# Buck.net
KiCad netlist of a schematic drawn in Altium Designer
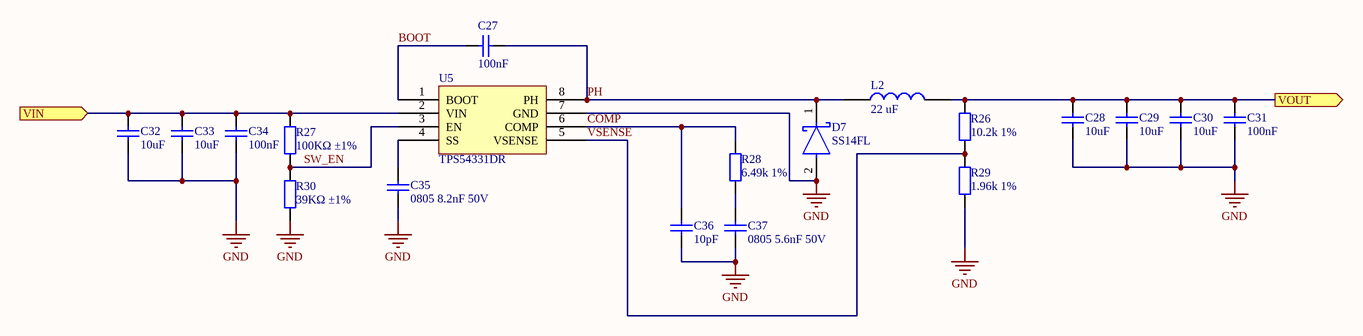
[diagram p0: Buck.SchDoc]

(export (version "E")
  (design (tool "Eeschema 10.0.6"))
  (components
    (comp (ref "C27")
      (value "100nF")
      (footprint "0603_C")
      (description "Chip capacitors")
      (fields (field (name "MANUFACTURER") "YAGEO") (field (name "PARTNUMBER") "CC0603KRX7R9BB104"))
      (libsource (lib "Miscellaneous Devices LC") (part "0603 100nF (104) 10% 50V"))
    )
    (comp (ref "C28")
      (value "10uF")
      (footprint "0603_C")
      (description "Chip capacitors")
      (fields
        (field (name "MANUFACTURER") "Samsung Electro-Mechanics")
        (field (name "PARTNUMBER") "CL10A106KP8NNNC")
      )
      (libsource (lib "Miscellaneous Devices LC") (part "0603 10uF (106) 10% 10V"))
    )
    (comp (ref "C29")
      (value "10uF")
      (footprint "0603_C")
      (description "Chip capacitors")
      (fields
        (field (name "MANUFACTURER") "Samsung Electro-Mechanics")
        (field (name "PARTNUMBER") "CL10A106KP8NNNC")
      )
      (libsource (lib "Miscellaneous Devices LC") (part "0603 10uF (106) 10% 10V"))
    )
    (comp (ref "C30")
      (value "10uF")
      (footprint "0603_C")
      (description "Chip capacitors")
      (fields
        (field (name "MANUFACTURER") "Samsung Electro-Mechanics")
        (field (name "PARTNUMBER") "CL10A106KP8NNNC")
      )
      (libsource (lib "Miscellaneous Devices LC") (part "0603 10uF (106) 10% 10V"))
    )
    (comp (ref "C31")
      (value "100nF")
      (footprint "0603_C")
      (description "Chip capacitors")
      (fields (field (name "MANUFACTURER") "YAGEO") (field (name "PARTNUMBER") "CC0603KRX7R9BB104"))
      (libsource (lib "Miscellaneous Devices LC") (part "0603 100nF (104) 10% 50V"))
    )
    (comp (ref "C32")
      (value "10uF")
      (footprint "0805_C")
      (description "Chip capacitors")
      (fields
        (field (name "MANUFACTURER") "Samsung Electro-Mechanics")
        (field (name "PARTNUMBER") "CL21A106KAYNNNE")
      )
      (libsource (lib "Miscellaneous Devices LC") (part "0805 10uF (106) 10% 25V"))
    )
    (comp (ref "C33")
      (value "10uF")
      (footprint "0805_C")
      (description "Chip capacitors")
      (fields
        (field (name "MANUFACTURER") "Samsung Electro-Mechanics")
        (field (name "PARTNUMBER") "CL21A106KAYNNNE")
      )
      (libsource (lib "Miscellaneous Devices LC") (part "0805 10uF (106) 10% 25V"))
    )
    (comp (ref "C34")
      (value "100nF")
      (footprint "0603_C")
      (description "Chip capacitors")
      (fields (field (name "MANUFACTURER") "YAGEO") (field (name "PARTNUMBER") "CC0603KRX7R9BB104"))
      (libsource (lib "Miscellaneous Devices LC") (part "0603 100nF (104) 10% 50V"))
    )
    (comp (ref "C35")
      (value "0805 8.2nF 50V")
      (footprint "Miscellaneous Devices LC:0805_C")
      (fields (field (name "PARTNUMBER") "CL21B822KBANNNC"))
      (libsource (lib "misc") (part "0805 8.2nF 50V"))
    )
    (comp (ref "C36")
      (value "10pF")
      (footprint "0603_C")
      (description "Chip capacitors")
      (fields
        (field (name "MANUFACTURER") "Samsung Electro-Mechanics")
        (field (name "PARTNUMBER") "CL10C100JB8NNNC")
      )
      (libsource (lib "Miscellaneous Devices LC") (part "0603 10pF (100) 5% 50V"))
    )
    (comp (ref "C37")
      (value "0805 5.6nF 50V")
      (footprint "Miscellaneous Devices LC:0805_C")
      (fields (field (name "PARTNUMBER") "CL21B562KBANNNC"))
      (libsource (lib "misc") (part "0805 5.6nF 50V"))
    )
    (comp (ref "D7")
      (value "SS14FL")
      (footprint "FP-425AD-MFG")
      (description "DIODE SCHOTTKY 40V 1A SOD123F")
      (fields
        (field (name "MANUFACTURER") "ON Semiconductor")
        (field (name "OCTOPART") "https://octopart.com/ss14fl-on+semiconductor-84331601")
      )
      (libsource (lib "Altium Content Vault") (part "c1678fac7984e62e0809fbf79c06691"))
    )
    (comp (ref "L2")
      (value "22 uF")
      (footprint "DR74:COBU-DR74-4R7-R_V")
      (libsource (lib "SWRB1204S-220MT") (part "SRP6540-5R6M"))
    )
    (comp (ref "R26")
      (value "10.2k 1%")
      (footprint "Miscellaneous Devices LC:1206_R")
      (fields (field (name "PARTNUMBER") "1206W4F1022T5E"))
      (libsource (lib "misc") (part "1206 10.2k 1%"))
    )
    (comp (ref "R27")
      (value "100KΩ ±1%")
      (footprint "0805_R")
      (description "Chip resistor")
      (fields (field (name "MANUFACTURER") "Uniroyal Elec") (field (name "POWER") "1/8W"))
      (libsource (lib "Miscellaneous Devices LC") (part "0805 100K (1003) 1%"))
    )
    (comp (ref "R28")
      (value "6.49k 1%")
      (footprint "Miscellaneous Devices LC:0805_R")
      (fields (field (name "PARTNUMBER") "0805W8F6491T5E"))
      (libsource (lib "misc") (part "0805 6.49k 1%"))
    )
    (comp (ref "R29")
      (value "1.96k 1%")
      (footprint "Miscellaneous Devices LC:1206_R")
      (fields (field (name "PARTNUMBER") "1206W4F1022T5E"))
      (libsource (lib "misc") (part "1206 1.96k 1%"))
    )
    (comp (ref "R30")
      (value "39KΩ ±1%")
      (footprint "0805_R")
      (description "Chip resistor")
      (fields (field (name "MANUFACTURER") "Uniroyal Elec") (field (name "POWER") "1/8W"))
      (libsource (lib "Miscellaneous Devices LC") (part "0805 39K (3902) 1%"))
    )
    (comp (ref "U5")
      (value "TPS54331DR")
      (footprint "SOIC-8_150mil")
      (description "DC-DC芯片")
      (libsource (lib "Miscellaneous Devices LC") (part "TPS54331DR_[C9865]"))
    )
  )
  (nets
    (net (code "1") (name "/BOOT") (class "Default")
      (node (ref "C27") (pin "2") (pinfunction "2_2") (pintype "passive"))
      (node (ref "U5") (pin "1") (pinfunction "BOOT_1") (pintype "passive"))
    )
    (net (code "2") (name "/COMP") (class "Default")
      (node (ref "C36") (pin "2") (pinfunction "2_2") (pintype "passive"))
      (node (ref "R28") (pin "2") (pinfunction "2_2") (pintype "passive"))
      (node (ref "U5") (pin "6") (pinfunction "COMP_6") (pintype "passive"))
    )
    (net (code "3") (name "/PH") (class "Default")
      (node (ref "C27") (pin "1") (pinfunction "1_1") (pintype "passive"))
      (node (ref "D7") (pin "1") (pinfunction "C_1") (pintype "passive"))
      (node (ref "L2") (pin "1") (pinfunction "1_1") (pintype "passive"))
      (node (ref "U5") (pin "8") (pinfunction "PH_8") (pintype "passive"))
    )
    (net (code "4") (name "/SW_EN") (class "Default")
      (node (ref "R27") (pin "2") (pinfunction "2_2") (pintype "passive"))
      (node (ref "R30") (pin "2") (pinfunction "2_2") (pintype "passive"))
      (node (ref "U5") (pin "3") (pinfunction "EN_3") (pintype "passive"))
    )
    (net (code "5") (name "/VIN") (class "Default")
      (node (ref "C32") (pin "2") (pinfunction "2_2") (pintype "passive"))
      (node (ref "C33") (pin "2") (pinfunction "2_2") (pintype "passive"))
      (node (ref "C34") (pin "2") (pinfunction "2_2") (pintype "passive"))
      (node (ref "R27") (pin "1") (pinfunction "1_1") (pintype "passive"))
      (node (ref "U5") (pin "2") (pinfunction "VIN_2") (pintype "passive"))
    )
    (net (code "6") (name "/VOUT") (class "Default")
      (node (ref "C28") (pin "2") (pinfunction "2_2") (pintype "passive"))
      (node (ref "C29") (pin "2") (pinfunction "2_2") (pintype "passive"))
      (node (ref "C30") (pin "2") (pinfunction "2_2") (pintype "passive"))
      (node (ref "C31") (pin "2") (pinfunction "2_2") (pintype "passive"))
      (node (ref "L2") (pin "2") (pinfunction "2_2") (pintype "passive"))
      (node (ref "R26") (pin "1") (pinfunction "1_1") (pintype "passive"))
    )
    (net (code "7") (name "/VSENSE") (class "Default")
      (node (ref "R26") (pin "2") (pinfunction "2_2") (pintype "passive"))
      (node (ref "R29") (pin "2") (pinfunction "2_2") (pintype "passive"))
      (node (ref "U5") (pin "5") (pinfunction "VSENSE_5") (pintype "passive"))
    )
    (net (code "8") (name "GND") (class "Default")
      (node (ref "C28") (pin "1") (pinfunction "1_1") (pintype "passive"))
      (node (ref "C29") (pin "1") (pinfunction "1_1") (pintype "passive"))
      (node (ref "C30") (pin "1") (pinfunction "1_1") (pintype "passive"))
      (node (ref "C31") (pin "1") (pinfunction "1_1") (pintype "passive"))
      (node (ref "C32") (pin "1") (pinfunction "1_1") (pintype "passive"))
      (node (ref "C33") (pin "1") (pinfunction "1_1") (pintype "passive"))
      (node (ref "C34") (pin "1") (pinfunction "1_1") (pintype "passive"))
      (node (ref "C35") (pin "1") (pinfunction "1_1") (pintype "passive"))
      (node (ref "C36") (pin "1") (pinfunction "1_1") (pintype "passive"))
      (node (ref "C37") (pin "1") (pinfunction "1_1") (pintype "passive"))
      (node (ref "D7") (pin "2") (pinfunction "A_2") (pintype "passive"))
      (node (ref "R29") (pin "1") (pinfunction "1_1") (pintype "passive"))
      (node (ref "R30") (pin "1") (pinfunction "1_1") (pintype "passive"))
      (node (ref "U5") (pin "7") (pinfunction "GND_7") (pintype "passive"))
    )
    (net (code "9") (name "Net-(C37-Pad2)") (class "Default")
      (node (ref "C37") (pin "2") (pinfunction "2_2") (pintype "passive"))
      (node (ref "R28") (pin "1") (pinfunction "1_1") (pintype "passive"))
    )
    (net (code "10") (name "Net-(U5-SS)") (class "Default")
      (node (ref "C35") (pin "2") (pinfunction "2_2") (pintype "passive"))
      (node (ref "U5") (pin "4") (pinfunction "SS_4") (pintype "passive"))
    )
  )
)
